# Prop_Module.net
KiCad netlist of a schematic drawn in EAGLE
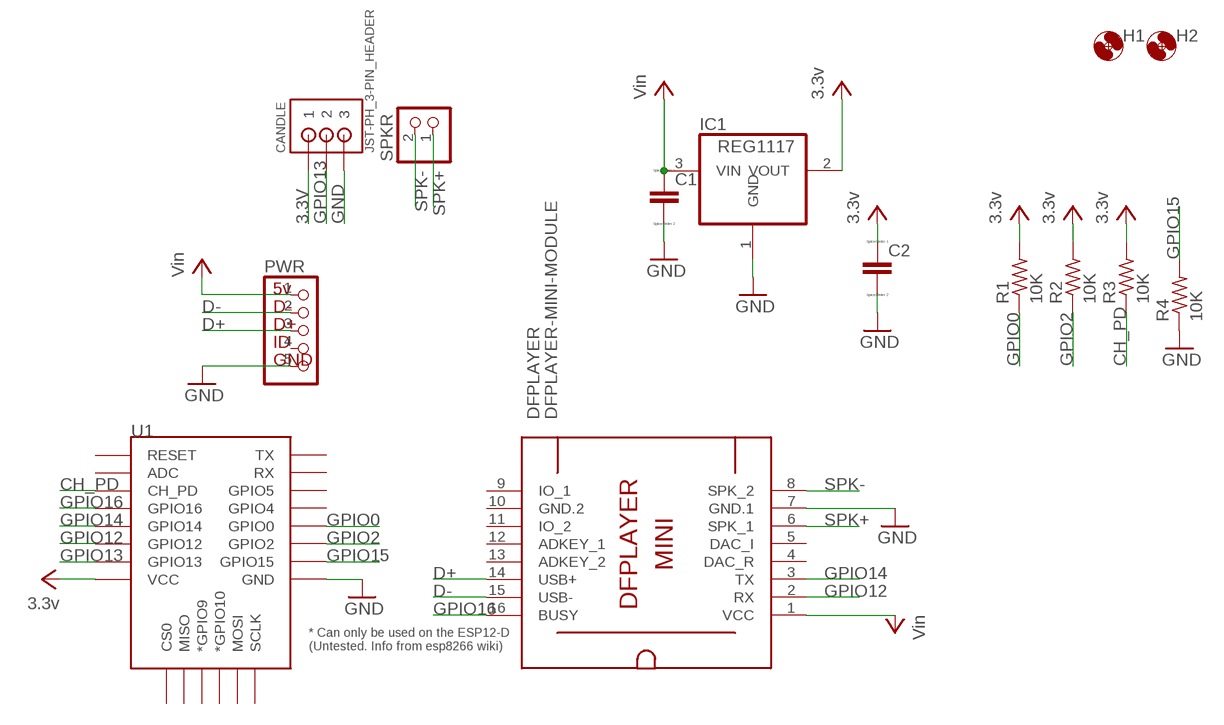
[diagram p0: schematic, sheet 1]

(export (version "E")
  (design (tool "Eeschema 10.0.6"))
  (components
    (comp (ref "C1") (value "C") (footprint "eagle-import:C0805") (libsource (lib "eagle-import") (part "C")))
    (comp (ref "C2") (value "C") (footprint "eagle-import:C0805") (libsource (lib "eagle-import") (part "C")))
    (comp (ref "CANDLE")
      (value "JST-PH_3-PIN_HEADER")
      (footprint "eagle-import:JST_B3B-PH_HEADER")
      (libsource (lib "eagle-import") (part "JST-PH_3-PIN_HEADER"))
    )
    (comp (ref "DFPLAYER")
      (value "DFPLAYER-MINI-MODULE")
      (footprint "eagle-import:DFPLAYER-MINI-MODULE")
      (libsource (lib "eagle-import") (part "DFPLAYER-MINI-MODULE"))
    )
    (comp (ref "H1")
      (value "MOUNT-HOLE3.2")
      (footprint "eagle-import:3,2")
      (libsource (lib "eagle-import") (part "MOUNT-HOLE3.2"))
    )
    (comp (ref "H2")
      (value "MOUNT-HOLE3.2")
      (footprint "eagle-import:3,2")
      (libsource (lib "eagle-import") (part "MOUNT-HOLE3.2"))
    )
    (comp (ref "IC1")
      (value "REG1117")
      (footprint "eagle-import:SOT223")
      (libsource (lib "eagle-import") (part "REG1117"))
    )
    (comp (ref "PWR")
      (value "USB_BRK-1X5")
      (footprint "eagle-import:1X05")
      (libsource (lib "eagle-import") (part "USB_BRK-1X5"))
    )
    (comp (ref "R1")
      (value "10K")
      (footprint "eagle-import:M1206")
      (libsource (lib "eagle-import") (part "R-US_M1206"))
    )
    (comp (ref "R2")
      (value "10K")
      (footprint "eagle-import:M1206")
      (libsource (lib "eagle-import") (part "R-US_M1206"))
    )
    (comp (ref "R3")
      (value "10K")
      (footprint "eagle-import:M1206")
      (libsource (lib "eagle-import") (part "R-US_M1206"))
    )
    (comp (ref "R4")
      (value "10K")
      (footprint "eagle-import:M1206")
      (libsource (lib "eagle-import") (part "R-US_M1206"))
    )
    (comp (ref "SPKR")
      (value "JST_2PIN-THM")
      (footprint "eagle-import:JST-PH-2-THM")
      (libsource (lib "eagle-import") (part "JST_2PIN-THM"))
    )
    (comp (ref "U1")
      (value "ESP12ESMD")
      (footprint "eagle-import:ESP12E-SMD")
      (libsource (lib "eagle-import") (part "ESP12ESMD"))
    )
  )
  (nets
    (net (code "1") (name "/CH_PD") (class "Default")
      (node (ref "R3") (pin "1") (pinfunction "1_1") (pintype "passive"))
      (node (ref "U1") (pin "CH_PD") (pinfunction "CH_PD_CH_PD") (pintype "bidirectional"))
    )
    (net (code "2") (name "/D+") (class "Default")
      (node (ref "DFPLAYER") (pin "14") (pinfunction "USB+_14") (pintype "bidirectional"))
      (node (ref "PWR") (pin "3") (pinfunction "3_3") (pintype "passive"))
    )
    (net (code "3") (name "/D-") (class "Default")
      (node (ref "DFPLAYER") (pin "15") (pinfunction "USB-_15") (pintype "bidirectional"))
      (node (ref "PWR") (pin "2") (pinfunction "2_2") (pintype "passive"))
    )
    (net (code "4") (name "/GND.2") (class "Default")
      (node (ref "DFPLAYER") (pin "10") (pinfunction "GND.2_10") (pintype "power_in"))
    )
    (net (code "5") (name "/GPIO0") (class "Default")
      (node (ref "R1") (pin "1") (pinfunction "1_1") (pintype "passive"))
      (node (ref "U1") (pin "GPIO0") (pinfunction "GPIO0_GPIO0") (pintype "bidirectional"))
    )
    (net (code "6") (name "/GPIO2") (class "Default")
      (node (ref "R2") (pin "1") (pinfunction "1_1") (pintype "passive"))
      (node (ref "U1") (pin "GPIO2") (pinfunction "GPIO2_GPIO2") (pintype "bidirectional"))
    )
    (net (code "7") (name "/GPIO12") (class "Default")
      (node (ref "DFPLAYER") (pin "2") (pinfunction "RX_2") (pintype "bidirectional"))
      (node (ref "U1") (pin "GPIO12") (pinfunction "GPIO12_GPIO12") (pintype "bidirectional"))
    )
    (net (code "8") (name "/GPIO13") (class "Default")
      (node (ref "CANDLE") (pin "P2") (pinfunction "2_P2") (pintype "bidirectional"))
      (node (ref "U1") (pin "GPIO13") (pinfunction "GPIO13_GPIO13") (pintype "bidirectional"))
    )
    (net (code "9") (name "/GPIO14") (class "Default")
      (node (ref "DFPLAYER") (pin "3") (pinfunction "TX_3") (pintype "bidirectional"))
      (node (ref "U1") (pin "GPIO14") (pinfunction "GPIO14_GPIO14") (pintype "bidirectional"))
    )
    (net (code "10") (name "/GPIO15") (class "Default")
      (node (ref "R4") (pin "2") (pinfunction "2_2") (pintype "passive"))
      (node (ref "U1") (pin "GPIO15") (pinfunction "GPIO15_GPIO15") (pintype "bidirectional"))
    )
    (net (code "11") (name "/GPIO16") (class "Default")
      (node (ref "DFPLAYER") (pin "16") (pinfunction "BUSY_16") (pintype "bidirectional"))
      (node (ref "U1") (pin "GPIO16") (pinfunction "GPIO16_GPIO16") (pintype "bidirectional"))
    )
    (net (code "12") (name "/SPK+") (class "Default")
      (node (ref "DFPLAYER") (pin "6") (pinfunction "SPK_1_6") (pintype "bidirectional"))
      (node (ref "SPKR") (pin "1") (pinfunction "2_1") (pintype "passive"))
    )
    (net (code "13") (name "/SPK-") (class "Default")
      (node (ref "DFPLAYER") (pin "8") (pinfunction "SPK_2_8") (pintype "bidirectional"))
      (node (ref "SPKR") (pin "2") (pinfunction "1_2") (pintype "passive"))
    )
    (net (code "14") (name "3.3v") (class "Default")
      (node (ref "C2") (pin "1") (pinfunction "1_1") (pintype "passive"))
      (node (ref "CANDLE") (pin "P1") (pinfunction "1_P1") (pintype "bidirectional"))
      (node (ref "IC1") (pin "2") (pinfunction "VOUT_2") (pintype "output"))
      (node (ref "R1") (pin "2") (pinfunction "2_2") (pintype "passive"))
      (node (ref "R2") (pin "2") (pinfunction "2_2") (pintype "passive"))
      (node (ref "R3") (pin "2") (pinfunction "2_2") (pintype "passive"))
      (node (ref "U1") (pin "VCC") (pinfunction "VCC_VCC") (pintype "bidirectional"))
    )
    (net (code "15") (name "GND") (class "Default")
      (node (ref "C1") (pin "2") (pinfunction "2_2") (pintype "passive"))
      (node (ref "C2") (pin "2") (pinfunction "2_2") (pintype "passive"))
      (node (ref "CANDLE") (pin "P3") (pinfunction "3_P3") (pintype "bidirectional"))
      (node (ref "DFPLAYER") (pin "7") (pinfunction "GND.1_7") (pintype "power_in"))
      (node (ref "IC1") (pin "1") (pinfunction "GND_1") (pintype "power_in"))
      (node (ref "PWR") (pin "5") (pinfunction "5_5") (pintype "passive"))
      (node (ref "R4") (pin "1") (pinfunction "1_1") (pintype "passive"))
      (node (ref "U1") (pin "GND") (pinfunction "GND_GND") (pintype "bidirectional"))
    )
    (net (code "16") (name "Vin") (class "Default")
      (node (ref "C1") (pin "1") (pinfunction "1_1") (pintype "passive"))
      (node (ref "DFPLAYER") (pin "1") (pinfunction "VCC_1") (pintype "power_in"))
      (node (ref "IC1") (pin "3") (pinfunction "VIN_3") (pintype "input"))
      (node (ref "PWR") (pin "1") (pinfunction "1_1") (pintype "passive"))
    )
    (net (code "17") (name "unconnected-(DFPLAYER-ADKEY_1-Pad12)") (class "Default")
      (node (ref "DFPLAYER") (pin "12") (pinfunction "ADKEY_1_12") (pintype "bidirectional"))
    )
    (net (code "18") (name "unconnected-(DFPLAYER-ADKEY_2-Pad13)") (class "Default")
      (node (ref "DFPLAYER") (pin "13") (pinfunction "ADKEY_2_13") (pintype "bidirectional"))
    )
    (net (code "19") (name "unconnected-(DFPLAYER-DAC_I-Pad5)") (class "Default")
      (node (ref "DFPLAYER") (pin "5") (pinfunction "DAC_I_5") (pintype "bidirectional"))
    )
    (net (code "20") (name "unconnected-(DFPLAYER-DAC_R-Pad4)") (class "Default")
      (node (ref "DFPLAYER") (pin "4") (pinfunction "DAC_R_4") (pintype "bidirectional"))
    )
    (net (code "21") (name "unconnected-(DFPLAYER-IO_1-Pad9)") (class "Default")
      (node (ref "DFPLAYER") (pin "9") (pinfunction "IO_1_9") (pintype "bidirectional"))
    )
    (net (code "22") (name "unconnected-(DFPLAYER-IO_2-Pad11)") (class "Default")
      (node (ref "DFPLAYER") (pin "11") (pinfunction "IO_2_11") (pintype "bidirectional"))
    )
    (net (code "23") (name "unconnected-(PWR-Pad4)") (class "Default")
      (node (ref "PWR") (pin "4") (pinfunction "4_4") (pintype "passive"))
    )
    (net (code "24") (name "unconnected-(U1-*GPIO9-PadGPIO9)") (class "Default")
      (node (ref "U1") (pin "GPIO9") (pinfunction "*GPIO9_GPIO9") (pintype "bidirectional"))
    )
    (net (code "25") (name "unconnected-(U1-*GPIO10-PadGPIO10)") (class "Default")
      (node (ref "U1") (pin "GPIO10") (pinfunction "*GPIO10_GPIO10") (pintype "bidirectional"))
    )
    (net (code "26") (name "unconnected-(U1-PadADC)") (class "Default")
      (node (ref "U1") (pin "ADC") (pinfunction "ADC_ADC") (pintype "bidirectional"))
    )
    (net (code "27") (name "unconnected-(U1-PadCS0)") (class "Default")
      (node (ref "U1") (pin "CS0") (pinfunction "CS0_CS0") (pintype "bidirectional"))
    )
    (net (code "28") (name "unconnected-(U1-PadGPIO4)") (class "Default")
      (node (ref "U1") (pin "GPIO4") (pinfunction "GPIO4_GPIO4") (pintype "bidirectional"))
    )
    (net (code "29") (name "unconnected-(U1-PadGPIO5)") (class "Default")
      (node (ref "U1") (pin "GPIO5") (pinfunction "GPIO5_GPIO5") (pintype "bidirectional"))
    )
    (net (code "30") (name "unconnected-(U1-PadMISO)") (class "Default")
      (node (ref "U1") (pin "MISO") (pinfunction "MISO_MISO") (pintype "bidirectional"))
    )
    (net (code "31") (name "unconnected-(U1-PadMOSI)") (class "Default")
      (node (ref "U1") (pin "MOSI") (pinfunction "MOSI_MOSI") (pintype "bidirectional"))
    )
    (net (code "32") (name "unconnected-(U1-PadRESET)") (class "Default")
      (node (ref "U1") (pin "RESET") (pinfunction "RESET_RESET") (pintype "bidirectional"))
    )
    (net (code "33") (name "unconnected-(U1-PadSCLK)") (class "Default")
      (node (ref "U1") (pin "SCLK") (pinfunction "SCLK_SCLK") (pintype "bidirectional"))
    )
    (net (code "34") (name "unconnected-(U1-RX-PadRXD0)") (class "Default")
      (node (ref "U1") (pin "RXD0") (pinfunction "RX_RXD0") (pintype "bidirectional"))
    )
    (net (code "35") (name "unconnected-(U1-TX-PadTXD0)") (class "Default")
      (node (ref "U1") (pin "TXD0") (pinfunction "TX_TXD0") (pintype "bidirectional"))
    )
  )
)
